# Final_Standalone_Arduino.net
KiCad netlist of a schematic drawn in EAGLE
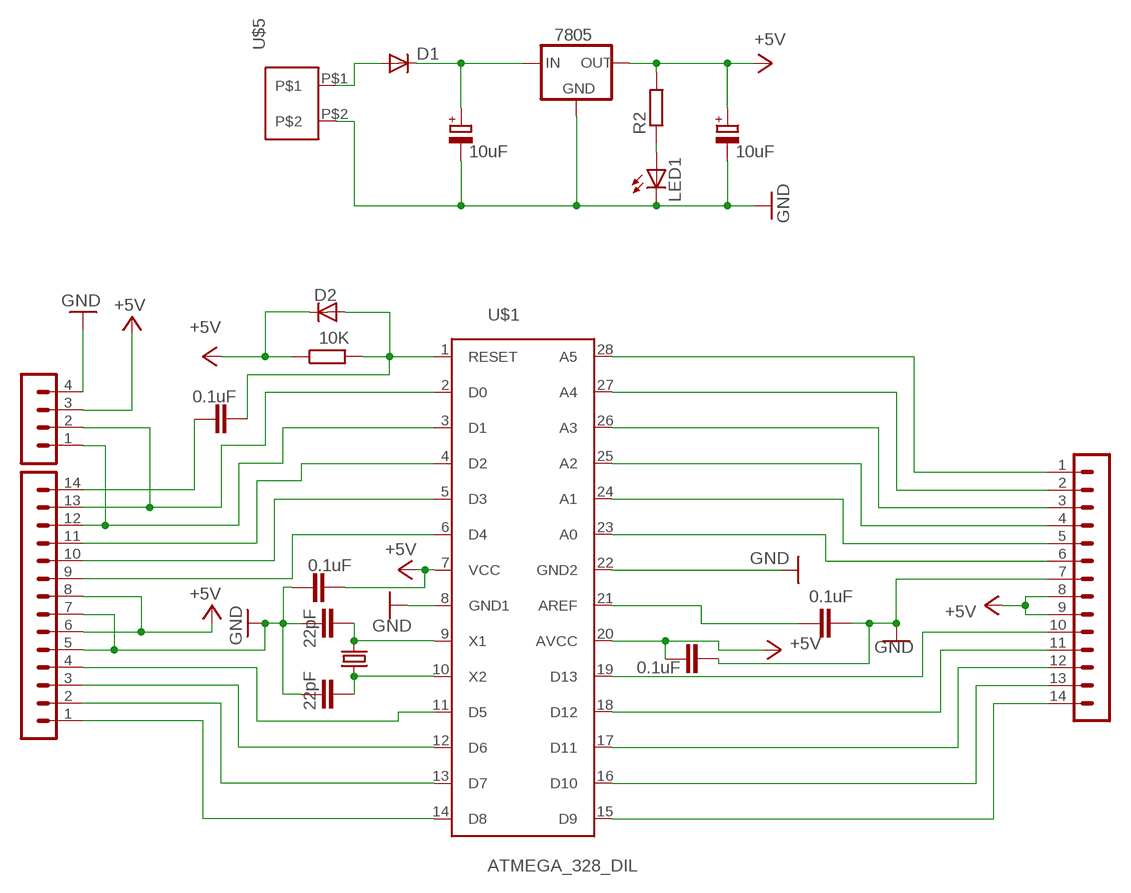
[diagram p0: schematic, sheet 1]

(export (version "E")
  (design (tool "Eeschema 10.0.6"))
  (components
    (comp (ref "C1")
      (value "22pF")
      (footprint "eagle-import:C025-024X044")
      (libsource (lib "eagle-import") (part "C-EU025-024X044"))
    )
    (comp (ref "C2")
      (value "22pF")
      (footprint "eagle-import:C025-024X044")
      (libsource (lib "eagle-import") (part "C-EU025-024X044"))
    )
    (comp (ref "C3")
      (value "0.1uF")
      (footprint "eagle-import:C025-024X044")
      (libsource (lib "eagle-import") (part "C-EU025-024X044"))
    )
    (comp (ref "C4")
      (value "10uF")
      (footprint "eagle-import:E2-5")
      (libsource (lib "eagle-import") (part "CPOL-EUE2-5"))
    )
    (comp (ref "C5")
      (value "0.1uF")
      (footprint "eagle-import:C025-024X044")
      (libsource (lib "eagle-import") (part "C-EU025-024X044"))
    )
    (comp (ref "C6")
      (value "0.1uF")
      (footprint "eagle-import:C025-024X044")
      (libsource (lib "eagle-import") (part "C-EU025-024X044"))
    )
    (comp (ref "C7")
      (value "0.1uF")
      (footprint "eagle-import:C025-024X044")
      (libsource (lib "eagle-import") (part "C-EU025-024X044"))
    )
    (comp (ref "C9")
      (value "10uF")
      (footprint "eagle-import:E2-5")
      (libsource (lib "eagle-import") (part "CPOL-EUE2-5"))
    )
    (comp (ref "D1")
      (value "DIODE-D-7.5")
      (footprint "eagle-import:D-7.5")
      (libsource (lib "eagle-import") (part "DIODE-D-7.5"))
    )
    (comp (ref "D2")
      (value "DIODE-D-7.5")
      (footprint "eagle-import:D-7.5")
      (libsource (lib "eagle-import") (part "DIODE-D-7.5"))
    )
    (comp (ref "IC2")
      (value "7805")
      (footprint "eagle-import:78XXL")
      (libsource (lib "eagle-import") (part "78XXL"))
    )
    (comp (ref "LED1")
      (value "LED5MM")
      (footprint "eagle-import:LED5MM")
      (libsource (lib "eagle-import") (part "LED5MM"))
    )
    (comp (ref "R1")
      (value "10K")
      (footprint "eagle-import:0207_10")
      (libsource (lib "eagle-import") (part "R-EU_0207/10"))
    )
    (comp (ref "R2")
      (value "R-EU_0207/10")
      (footprint "eagle-import:0207_10")
      (libsource (lib "eagle-import") (part "R-EU_0207/10"))
    )
    (comp (ref "U$1")
      (value "ATMEGA_328_DIL")
      (footprint "eagle-import:ATMEGA_328_DIL")
      (libsource (lib "eagle-import") (part "ATMEGA_328_DIL"))
    )
    (comp (ref "U$2")
      (value "14_PIN_CONN")
      (footprint "eagle-import:14_PIN_CONN")
      (libsource (lib "eagle-import") (part "14_PIN_CONN"))
    )
    (comp (ref "U$3")
      (value "14_PIN_CONN")
      (footprint "eagle-import:14_PIN_CONN")
      (libsource (lib "eagle-import") (part "14_PIN_CONN"))
    )
    (comp (ref "U$4")
      (value "4_PIN_CONN")
      (footprint "eagle-import:4_PIN_CONN")
      (libsource (lib "eagle-import") (part "4_PIN_CONN"))
    )
    (comp (ref "U$5")
      (value "2_PIN_SCREW_CONN")
      (footprint "eagle-import:2_PIN_SCREW_CONN")
      (libsource (lib "eagle-import") (part "2_PIN_SCREW_CONN"))
    )
    (comp (ref "Y1")
      (value "CRYSTALHC49UV")
      (footprint "eagle-import:HC49U-V")
      (libsource (lib "eagle-import") (part "CRYSTALHC49UV"))
    )
  )
  (nets
    (net (code "1") (name "+5V") (class "Default")
      (node (ref "C3") (pin "2") (pinfunction "2_2") (pintype "passive"))
      (node (ref "C5") (pin "2") (pinfunction "2_2") (pintype "passive"))
      (node (ref "C9") (pin "+") (pinfunction "+_+") (pintype "passive"))
      (node (ref "D2") (pin "C") (pinfunction "C_C") (pintype "passive"))
      (node (ref "IC2") (pin "OUT") (pinfunction "OUT_OUT") (pintype "passive"))
      (node (ref "R1") (pin "1") (pinfunction "1_1") (pintype "passive"))
      (node (ref "R2") (pin "2") (pinfunction "2_2") (pintype "passive"))
      (node (ref "U$1") (pin "20") (pinfunction "AVCC_20") (pintype "bidirectional"))
      (node (ref "U$1") (pin "7") (pinfunction "VCC_7") (pintype "bidirectional"))
      (node (ref "U$2") (pin "6") (pinfunction "6_6") (pintype "passive"))
      (node (ref "U$2") (pin "8") (pinfunction "8_8") (pintype "passive"))
      (node (ref "U$3") (pin "8") (pinfunction "8_8") (pintype "passive"))
      (node (ref "U$3") (pin "9") (pinfunction "9_9") (pintype "passive"))
      (node (ref "U$4") (pin "3") (pinfunction "3_3") (pintype "bidirectional"))
    )
    (net (code "2") (name "GND") (class "Default")
      (node (ref "C1") (pin "1") (pinfunction "1_1") (pintype "passive"))
      (node (ref "C2") (pin "1") (pinfunction "1_1") (pintype "passive"))
      (node (ref "C3") (pin "1") (pinfunction "1_1") (pintype "passive"))
      (node (ref "C4") (pin "-") (pinfunction "-_-") (pintype "passive"))
      (node (ref "C5") (pin "1") (pinfunction "1_1") (pintype "passive"))
      (node (ref "C7") (pin "1") (pinfunction "1_1") (pintype "passive"))
      (node (ref "C9") (pin "-") (pinfunction "-_-") (pintype "passive"))
      (node (ref "IC2") (pin "GND") (pinfunction "GND_GND") (pintype "input"))
      (node (ref "LED1") (pin "K") (pinfunction "C_K") (pintype "passive"))
      (node (ref "U$1") (pin "22") (pinfunction "GND2_22") (pintype "bidirectional"))
      (node (ref "U$1") (pin "8") (pinfunction "GND1_8") (pintype "bidirectional"))
      (node (ref "U$2") (pin "5") (pinfunction "5_5") (pintype "passive"))
      (node (ref "U$2") (pin "7") (pinfunction "7_7") (pintype "passive"))
      (node (ref "U$3") (pin "7") (pinfunction "7_7") (pintype "passive"))
      (node (ref "U$4") (pin "4") (pinfunction "4_4") (pintype "bidirectional"))
      (node (ref "U$5") (pin "P$2") (pinfunction "P$2_P$2") (pintype "bidirectional"))
    )
    (net (code "3") (name "Net-(C4-Pad+)") (class "Default")
      (node (ref "C4") (pin "+") (pinfunction "+_+") (pintype "passive"))
      (node (ref "D1") (pin "C") (pinfunction "C_C") (pintype "passive"))
      (node (ref "IC2") (pin "IN") (pinfunction "IN_IN") (pintype "input"))
    )
    (net (code "4") (name "Net-(C6-Pad1)") (class "Default")
      (node (ref "C6") (pin "1") (pinfunction "1_1") (pintype "passive"))
      (node (ref "U$2") (pin "14") (pinfunction "14_14") (pintype "passive"))
    )
    (net (code "5") (name "Net-(D1-PadA)") (class "Default")
      (node (ref "D1") (pin "A") (pinfunction "A_A") (pintype "passive"))
      (node (ref "U$5") (pin "P$1") (pinfunction "P$1_P$1") (pintype "bidirectional"))
    )
    (net (code "6") (name "Net-(LED1-PadA)") (class "Default")
      (node (ref "LED1") (pin "A") (pinfunction "A_A") (pintype "passive"))
      (node (ref "R2") (pin "1") (pinfunction "1_1") (pintype "passive"))
    )
    (net (code "7") (name "Net-(U$1-A0)") (class "Default")
      (node (ref "U$1") (pin "23") (pinfunction "A0_23") (pintype "bidirectional"))
      (node (ref "U$3") (pin "6") (pinfunction "6_6") (pintype "passive"))
    )
    (net (code "8") (name "Net-(U$1-A1)") (class "Default")
      (node (ref "U$1") (pin "24") (pinfunction "A1_24") (pintype "bidirectional"))
      (node (ref "U$3") (pin "5") (pinfunction "5_5") (pintype "passive"))
    )
    (net (code "9") (name "Net-(U$1-A2)") (class "Default")
      (node (ref "U$1") (pin "25") (pinfunction "A2_25") (pintype "bidirectional"))
      (node (ref "U$3") (pin "4") (pinfunction "4_4") (pintype "passive"))
    )
    (net (code "10") (name "Net-(U$1-A3)") (class "Default")
      (node (ref "U$1") (pin "26") (pinfunction "A3_26") (pintype "bidirectional"))
      (node (ref "U$3") (pin "3") (pinfunction "3_3") (pintype "passive"))
    )
    (net (code "11") (name "Net-(U$1-A4)") (class "Default")
      (node (ref "U$1") (pin "27") (pinfunction "A4_27") (pintype "bidirectional"))
      (node (ref "U$3") (pin "2") (pinfunction "2_2") (pintype "passive"))
    )
    (net (code "12") (name "Net-(U$1-A5)") (class "Default")
      (node (ref "U$1") (pin "28") (pinfunction "A5_28") (pintype "bidirectional"))
      (node (ref "U$3") (pin "1") (pinfunction "1_1") (pintype "passive"))
    )
    (net (code "13") (name "Net-(U$1-AREF)") (class "Default")
      (node (ref "C7") (pin "2") (pinfunction "2_2") (pintype "passive"))
      (node (ref "U$1") (pin "21") (pinfunction "AREF_21") (pintype "bidirectional"))
    )
    (net (code "14") (name "Net-(U$1-D0)") (class "Default")
      (node (ref "U$1") (pin "2") (pinfunction "D0_2") (pintype "bidirectional"))
      (node (ref "U$2") (pin "13") (pinfunction "13_13") (pintype "passive"))
      (node (ref "U$4") (pin "2") (pinfunction "2_2") (pintype "bidirectional"))
    )
    (net (code "15") (name "Net-(U$1-D1)") (class "Default")
      (node (ref "U$1") (pin "3") (pinfunction "D1_3") (pintype "bidirectional"))
      (node (ref "U$2") (pin "12") (pinfunction "12_12") (pintype "passive"))
      (node (ref "U$4") (pin "1") (pinfunction "1_1") (pintype "bidirectional"))
    )
    (net (code "16") (name "Net-(U$1-D2)") (class "Default")
      (node (ref "U$1") (pin "4") (pinfunction "D2_4") (pintype "bidirectional"))
      (node (ref "U$2") (pin "11") (pinfunction "11_11") (pintype "passive"))
    )
    (net (code "17") (name "Net-(U$1-D3)") (class "Default")
      (node (ref "U$1") (pin "5") (pinfunction "D3_5") (pintype "bidirectional"))
      (node (ref "U$2") (pin "10") (pinfunction "10_10") (pintype "passive"))
    )
    (net (code "18") (name "Net-(U$1-D4)") (class "Default")
      (node (ref "U$1") (pin "6") (pinfunction "D4_6") (pintype "bidirectional"))
      (node (ref "U$2") (pin "9") (pinfunction "9_9") (pintype "passive"))
    )
    (net (code "19") (name "Net-(U$1-D5)") (class "Default")
      (node (ref "U$1") (pin "11") (pinfunction "D5_11") (pintype "bidirectional"))
      (node (ref "U$2") (pin "4") (pinfunction "4_4") (pintype "passive"))
    )
    (net (code "20") (name "Net-(U$1-D6)") (class "Default")
      (node (ref "U$1") (pin "12") (pinfunction "D6_12") (pintype "bidirectional"))
      (node (ref "U$2") (pin "3") (pinfunction "3_3") (pintype "passive"))
    )
    (net (code "21") (name "Net-(U$1-D7)") (class "Default")
      (node (ref "U$1") (pin "13") (pinfunction "D7_13") (pintype "bidirectional"))
      (node (ref "U$2") (pin "2") (pinfunction "2_2") (pintype "passive"))
    )
    (net (code "22") (name "Net-(U$1-D8)") (class "Default")
      (node (ref "U$1") (pin "14") (pinfunction "D8_14") (pintype "bidirectional"))
      (node (ref "U$2") (pin "1") (pinfunction "1_1") (pintype "passive"))
    )
    (net (code "23") (name "Net-(U$1-D9)") (class "Default")
      (node (ref "U$1") (pin "15") (pinfunction "D9_15") (pintype "bidirectional"))
      (node (ref "U$3") (pin "14") (pinfunction "14_14") (pintype "passive"))
    )
    (net (code "24") (name "Net-(U$1-D10)") (class "Default")
      (node (ref "U$1") (pin "16") (pinfunction "D10_16") (pintype "bidirectional"))
      (node (ref "U$3") (pin "13") (pinfunction "13_13") (pintype "passive"))
    )
    (net (code "25") (name "Net-(U$1-D11)") (class "Default")
      (node (ref "U$1") (pin "17") (pinfunction "D11_17") (pintype "bidirectional"))
      (node (ref "U$3") (pin "12") (pinfunction "12_12") (pintype "passive"))
    )
    (net (code "26") (name "Net-(U$1-D12)") (class "Default")
      (node (ref "U$1") (pin "18") (pinfunction "D12_18") (pintype "bidirectional"))
      (node (ref "U$3") (pin "11") (pinfunction "11_11") (pintype "passive"))
    )
    (net (code "27") (name "Net-(U$1-D13)") (class "Default")
      (node (ref "U$1") (pin "19") (pinfunction "D13_19") (pintype "bidirectional"))
      (node (ref "U$3") (pin "10") (pinfunction "10_10") (pintype "passive"))
    )
    (net (code "28") (name "Net-(U$1-RESET)") (class "Default")
      (node (ref "C6") (pin "2") (pinfunction "2_2") (pintype "passive"))
      (node (ref "D2") (pin "A") (pinfunction "A_A") (pintype "passive"))
      (node (ref "R1") (pin "2") (pinfunction "2_2") (pintype "passive"))
      (node (ref "U$1") (pin "1") (pinfunction "RESET_1") (pintype "bidirectional"))
    )
    (net (code "29") (name "Net-(U$1-X1)") (class "Default")
      (node (ref "C1") (pin "2") (pinfunction "2_2") (pintype "passive"))
      (node (ref "U$1") (pin "9") (pinfunction "X1_9") (pintype "bidirectional"))
      (node (ref "Y1") (pin "2") (pinfunction "2_2") (pintype "passive"))
    )
    (net (code "30") (name "Net-(U$1-X2)") (class "Default")
      (node (ref "C2") (pin "2") (pinfunction "2_2") (pintype "passive"))
      (node (ref "U$1") (pin "10") (pinfunction "X2_10") (pintype "bidirectional"))
      (node (ref "Y1") (pin "1") (pinfunction "1_1") (pintype "passive"))
    )
  )
)
